# ProPrj___2024-08-31.net
KiCad netlist of a schematic drawn in EasyEDA Pro
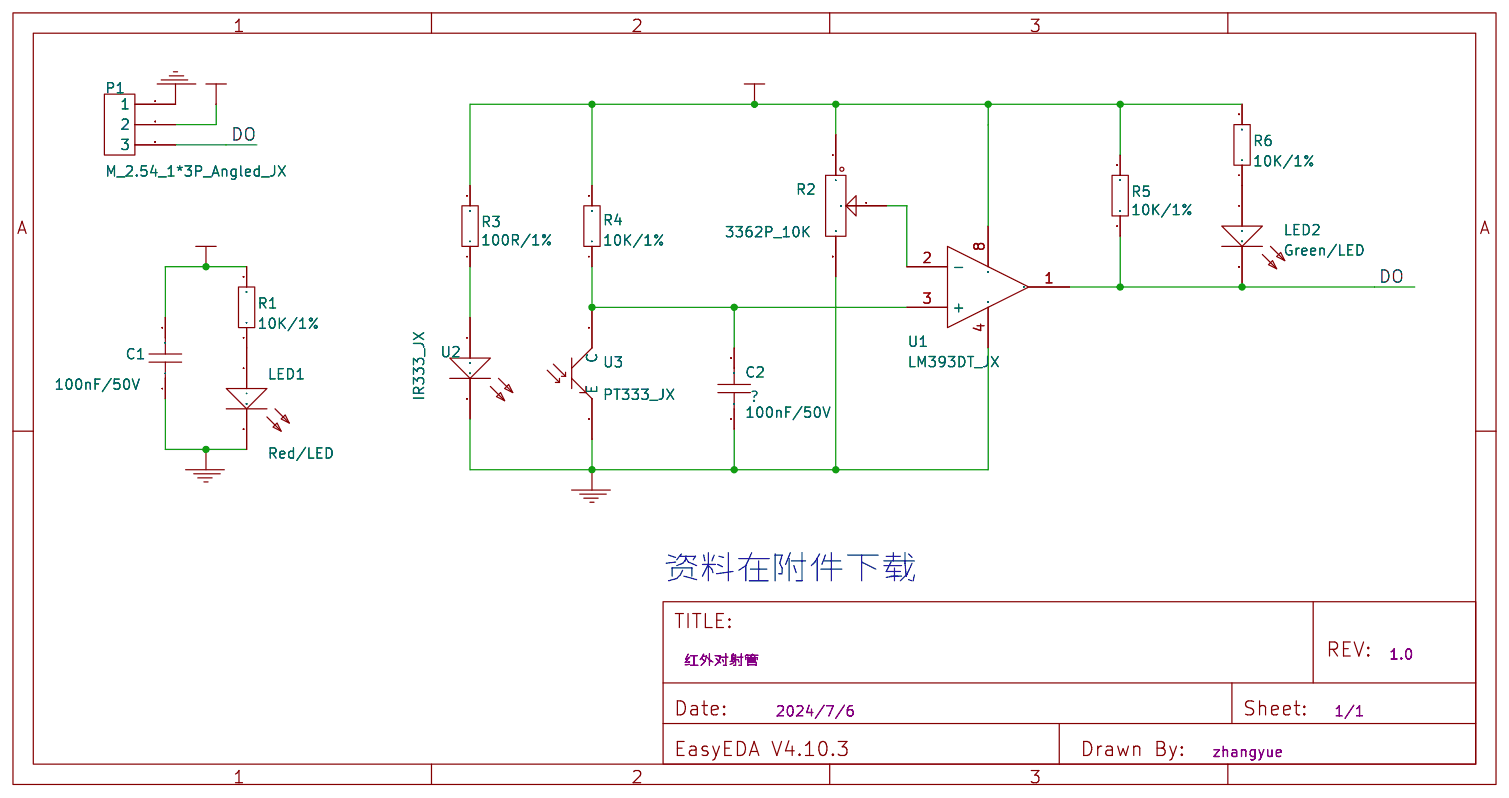
[diagram p0: schematic sheet]

(export (version "E")
  (design (tool "Eeschema 10.0.6"))
  (components
    (comp (ref "C1")
      (value "100nF/50V")
      (footprint "easyedapro:0603_C_JX")
      (libsource (lib "easyedapro") (part "100nF/50V"))
    )
    (comp (ref "C2")
      (value "100nF/50V")
      (footprint "easyedapro:0603_C_JX")
      (libsource (lib "easyedapro") (part "100nF/50V"))
    )
    (comp (ref "LED1")
      (value "Red/LED")
      (footprint "easyedapro:0603_D_JX")
      (libsource (lib "easyedapro") (part "Red/LED"))
    )
    (comp (ref "LED2")
      (value "Green/LED")
      (footprint "easyedapro:0603_D_JX")
      (libsource (lib "easyedapro") (part "Green/LED"))
    )
    (comp (ref "P1")
      (value "M_2.54_1*3P_Angled_JX")
      (footprint "easyedapro:2.54-1*3P_tight_JX")
      (libsource (lib "easyedapro") (part "M_2.54_1*3P_Angled_JX"))
    )
    (comp (ref "R1")
      (value "10K/1%")
      (footprint "easyedapro:0603_R_JX")
      (libsource (lib "easyedapro") (part "10K/1%"))
    )
    (comp (ref "R2")
      (value "3362P_10K")
      (footprint "easyedapro:3362P_Corr_JX")
      (libsource (lib "easyedapro") (part "3362P_10K"))
    )
    (comp (ref "R3")
      (value "100R/1%")
      (footprint "easyedapro:0603_R_JX")
      (libsource (lib "easyedapro") (part "100R/1%"))
    )
    (comp (ref "R4")
      (value "10K/1%")
      (footprint "easyedapro:0603_R_JX")
      (libsource (lib "easyedapro") (part "10K/1%"))
    )
    (comp (ref "R5")
      (value "10K/1%")
      (footprint "easyedapro:0603_R_JX")
      (libsource (lib "easyedapro") (part "10K/1%"))
    )
    (comp (ref "R6")
      (value "10K/1%")
      (footprint "easyedapro:0603_R_JX")
      (libsource (lib "easyedapro") (part "10K/1%"))
    )
    (comp (ref "U1") (value "LM393DT_JX") (libsource (lib "easyedapro") (part "LM393DT_JX")))
    (comp (ref "U2")
      (value "IR333_JX")
      (footprint "easyedapro:LED_D5.0mm_Horizontal_O3.81_JX")
      (libsource (lib "easyedapro") (part "IR333_JX"))
    )
    (comp (ref "U3")
      (value "PT333_JX")
      (footprint "easyedapro:PT333-3B-L-5mm_Horizontal_JX")
      (libsource (lib "easyedapro") (part "PT333_JX"))
    )
  )
  (nets
    (net (code "1") (name "/DO") (class "Default")
      (node (ref "LED2") (pin "2") (pinfunction "C_2") (pintype "input"))
      (node (ref "P1") (pin "3") (pinfunction "3_3") (pintype "unspecified"))
      (node (ref "R5") (pin "1") (pinfunction "1_1") (pintype "unspecified"))
      (node (ref "U1") (pin "1") (pinfunction "1_1") (pintype "unspecified"))
    )
    (net (code "2") (name "GND") (class "Default")
      (node (ref "C1") (pin "1") (pinfunction "1_1") (pintype "unspecified"))
      (node (ref "C2") (pin "1") (pinfunction "1_1") (pintype "unspecified"))
      (node (ref "LED1") (pin "2") (pinfunction "C_2") (pintype "input"))
      (node (ref "P1") (pin "1") (pinfunction "1_1") (pintype "unspecified"))
      (node (ref "R2") (pin "3") (pinfunction "3_3") (pintype "unspecified"))
      (node (ref "U1") (pin "4") (pinfunction "8_4") (pintype "unspecified"))
      (node (ref "U2") (pin "2") (pinfunction "C_2") (pintype "input"))
      (node (ref "U3") (pin "1") (pinfunction "E_1") (pintype "unspecified"))
    )
    (net (code "3") (name "Net-(LED1-A)") (class "Default")
      (node (ref "LED1") (pin "1") (pinfunction "A_1") (pintype "input"))
      (node (ref "R1") (pin "1") (pinfunction "1_1") (pintype "unspecified"))
    )
    (net (code "4") (name "Net-(LED2-A)") (class "Default")
      (node (ref "LED2") (pin "1") (pinfunction "A_1") (pintype "input"))
      (node (ref "R6") (pin "1") (pinfunction "1_1") (pintype "unspecified"))
    )
    (net (code "5") (name "Net-(U1-+)") (class "Default")
      (node (ref "C2") (pin "2") (pinfunction "2_2") (pintype "unspecified"))
      (node (ref "R4") (pin "1") (pinfunction "1_1") (pintype "unspecified"))
      (node (ref "U1") (pin "3") (pinfunction "+_3") (pintype "unspecified"))
      (node (ref "U3") (pin "2") (pinfunction "C_2") (pintype "unspecified"))
    )
    (net (code "6") (name "Net-(U1--)") (class "Default")
      (node (ref "R2") (pin "2") (pinfunction "2_2") (pintype "unspecified"))
      (node (ref "U1") (pin "2") (pinfunction "-_2") (pintype "unspecified"))
    )
    (net (code "7") (name "Net-(U2-A)") (class "Default")
      (node (ref "R3") (pin "1") (pinfunction "1_1") (pintype "unspecified"))
      (node (ref "U2") (pin "1") (pinfunction "A_1") (pintype "input"))
    )
    (net (code "8") (name "VCC") (class "Default")
      (node (ref "C1") (pin "2") (pinfunction "2_2") (pintype "unspecified"))
      (node (ref "P1") (pin "2") (pinfunction "2_2") (pintype "unspecified"))
      (node (ref "R1") (pin "2") (pinfunction "2_2") (pintype "unspecified"))
      (node (ref "R2") (pin "1") (pinfunction "1_1") (pintype "unspecified"))
      (node (ref "R3") (pin "2") (pinfunction "2_2") (pintype "unspecified"))
      (node (ref "R4") (pin "2") (pinfunction "2_2") (pintype "unspecified"))
      (node (ref "R5") (pin "2") (pinfunction "2_2") (pintype "unspecified"))
      (node (ref "R6") (pin "2") (pinfunction "2_2") (pintype "unspecified"))
      (node (ref "U1") (pin "8") (pinfunction "8_8") (pintype "unspecified"))
    )
  )
)
